# POW_HUB.net
KiCad netlist of a schematic drawn in EAGLE
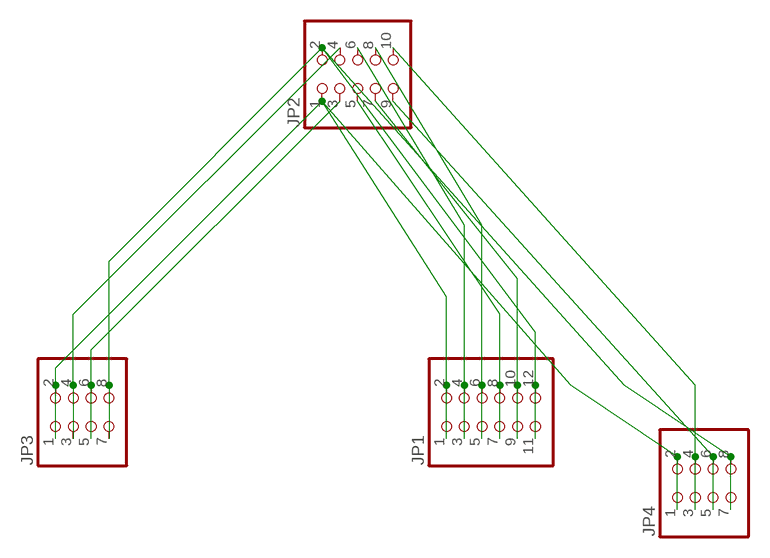
[diagram p0: schematic, sheet 1]

(export (version "E")
  (design (tool "Eeschema 10.0.6"))
  (components
    (comp (ref "JP1")
      (value "PINHD-2X6")
      (footprint "eagle-import:2X06")
      (libsource (lib "eagle-import") (part "PINHD-2X6"))
    )
    (comp (ref "JP2")
      (value "PINHD-2X5")
      (footprint "eagle-import:2X05")
      (libsource (lib "eagle-import") (part "PINHD-2X5"))
    )
    (comp (ref "JP3")
      (value "PINHD-2X4")
      (footprint "eagle-import:2X04")
      (libsource (lib "eagle-import") (part "PINHD-2X4"))
    )
    (comp (ref "JP4")
      (value "PINHD-2X4")
      (footprint "eagle-import:2X04")
      (libsource (lib "eagle-import") (part "PINHD-2X4"))
    )
  )
  (nets
    (net (code "1") (name "Net-(JP1-Pad1)") (class "Default")
      (node (ref "JP1") (pin "1") (pinfunction "1_1") (pintype "passive"))
      (node (ref "JP1") (pin "2") (pinfunction "2_2") (pintype "passive"))
      (node (ref "JP2") (pin "1") (pinfunction "1_1") (pintype "passive"))
      (node (ref "JP3") (pin "1") (pinfunction "1_1") (pintype "passive"))
      (node (ref "JP3") (pin "2") (pinfunction "2_2") (pintype "passive"))
      (node (ref "JP4") (pin "1") (pinfunction "1_1") (pintype "passive"))
      (node (ref "JP4") (pin "2") (pinfunction "2_2") (pintype "passive"))
    )
    (net (code "2") (name "Net-(JP1-Pad3)") (class "Default")
      (node (ref "JP1") (pin "3") (pinfunction "3_3") (pintype "passive"))
      (node (ref "JP1") (pin "4") (pinfunction "4_4") (pintype "passive"))
      (node (ref "JP2") (pin "6") (pinfunction "6_6") (pintype "passive"))
    )
    (net (code "3") (name "Net-(JP1-Pad5)") (class "Default")
      (node (ref "JP1") (pin "5") (pinfunction "5_5") (pintype "passive"))
      (node (ref "JP1") (pin "6") (pinfunction "6_6") (pintype "passive"))
      (node (ref "JP2") (pin "8") (pinfunction "8_8") (pintype "passive"))
    )
    (net (code "4") (name "Net-(JP1-Pad7)") (class "Default")
      (node (ref "JP1") (pin "7") (pinfunction "7_7") (pintype "passive"))
      (node (ref "JP1") (pin "8") (pinfunction "8_8") (pintype "passive"))
      (node (ref "JP2") (pin "5") (pinfunction "5_5") (pintype "passive"))
    )
    (net (code "5") (name "Net-(JP1-Pad10)") (class "Default")
      (node (ref "JP1") (pin "10") (pinfunction "10_10") (pintype "passive"))
      (node (ref "JP1") (pin "9") (pinfunction "9_9") (pintype "passive"))
      (node (ref "JP2") (pin "7") (pinfunction "7_7") (pintype "passive"))
    )
    (net (code "6") (name "Net-(JP1-Pad11)") (class "Default")
      (node (ref "JP1") (pin "11") (pinfunction "11_11") (pintype "passive"))
      (node (ref "JP1") (pin "12") (pinfunction "12_12") (pintype "passive"))
      (node (ref "JP2") (pin "2") (pinfunction "2_2") (pintype "passive"))
      (node (ref "JP3") (pin "7") (pinfunction "7_7") (pintype "passive"))
      (node (ref "JP3") (pin "8") (pinfunction "8_8") (pintype "passive"))
      (node (ref "JP4") (pin "7") (pinfunction "7_7") (pintype "passive"))
      (node (ref "JP4") (pin "8") (pinfunction "8_8") (pintype "passive"))
    )
    (net (code "7") (name "Net-(JP2-Pad3)") (class "Default")
      (node (ref "JP2") (pin "3") (pinfunction "3_3") (pintype "passive"))
      (node (ref "JP3") (pin "5") (pinfunction "5_5") (pintype "passive"))
      (node (ref "JP3") (pin "6") (pinfunction "6_6") (pintype "passive"))
    )
    (net (code "8") (name "Net-(JP2-Pad4)") (class "Default")
      (node (ref "JP2") (pin "4") (pinfunction "4_4") (pintype "passive"))
      (node (ref "JP3") (pin "3") (pinfunction "3_3") (pintype "passive"))
      (node (ref "JP3") (pin "4") (pinfunction "4_4") (pintype "passive"))
    )
    (net (code "9") (name "Net-(JP2-Pad9)") (class "Default")
      (node (ref "JP2") (pin "9") (pinfunction "9_9") (pintype "passive"))
      (node (ref "JP4") (pin "5") (pinfunction "5_5") (pintype "passive"))
      (node (ref "JP4") (pin "6") (pinfunction "6_6") (pintype "passive"))
    )
    (net (code "10") (name "Net-(JP2-Pad10)") (class "Default")
      (node (ref "JP2") (pin "10") (pinfunction "10_10") (pintype "passive"))
      (node (ref "JP4") (pin "3") (pinfunction "3_3") (pintype "passive"))
      (node (ref "JP4") (pin "4") (pinfunction "4_4") (pintype "passive"))
    )
  )
)
